# GAL.net
KiCad netlist of a schematic drawn in Altium Designer
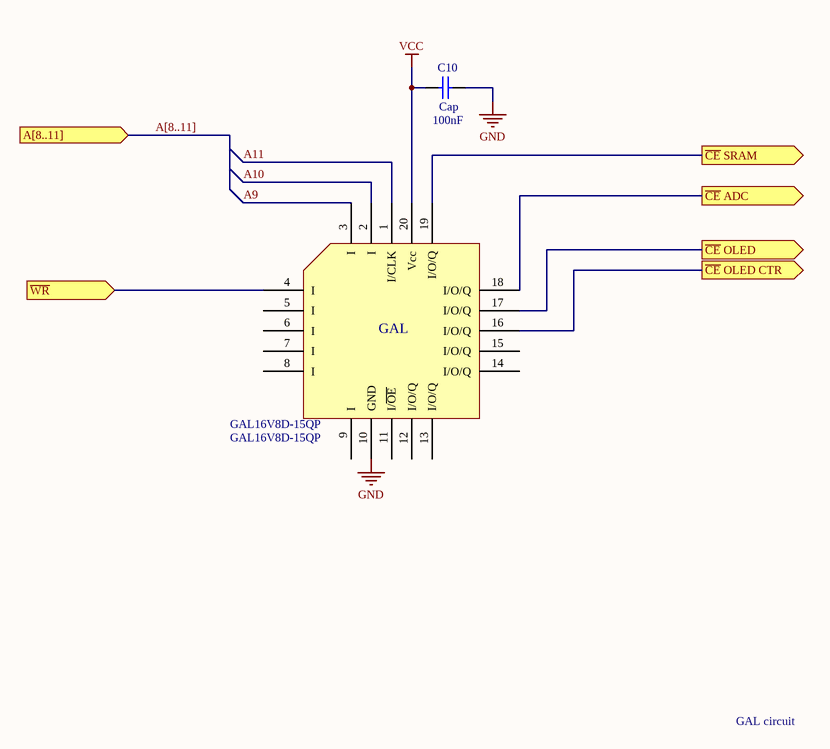
[diagram p0: GAL.SchDoc]

(export (version "E")
  (design (tool "Eeschema 10.0.6"))
  (components
    (comp (ref "C10")
      (value "Cap")
      (footprint "C1210")
      (description "Capacitor (Semiconductor SIM Model)")
      (fields (field (name "ALTIUM_VALUE") "100nF") (field (name "PUBLISHER") "Altium Limited"))
      (libsource (lib "Miscellaneous Devices") (part "Cap Semi"))
    )
    (comp (ref "GAL16V8D-15QP")
      (value "GAL16V8D-15QP")
      (footprint "GAL 16V8D-10LJ/-10QL PLCC 20-PIN")
      (description "GAL - Generic Array Logic")
      (libsource (lib "IIDKLib") (part "GAL16V8D-15QP"))
    )
  )
  (nets
    (net (code "2") (name "/A9") (class "Default")
      (node (ref "GAL16V8D-15QP") (pin "3") (pinfunction "I_3") (pintype "passive"))
    )
    (net (code "3") (name "/A10") (class "Default")
      (node (ref "GAL16V8D-15QP") (pin "2") (pinfunction "I_2") (pintype "passive"))
    )
    (net (code "4") (name "/A11") (class "Default")
      (node (ref "GAL16V8D-15QP") (pin "1") (pinfunction "I/CLK_1") (pintype "passive"))
    )
    (net (code "6") (name "/~{CE} ADC") (class "Default")
      (node (ref "GAL16V8D-15QP") (pin "18") (pinfunction "I/O/Q_18") (pintype "passive"))
    )
    (net (code "7") (name "/~{CE} OLED") (class "Default")
      (node (ref "GAL16V8D-15QP") (pin "17") (pinfunction "I/O/Q_17") (pintype "passive"))
    )
    (net (code "8") (name "/~{CE} OLED CTR") (class "Default")
      (node (ref "GAL16V8D-15QP") (pin "16") (pinfunction "I/O/Q_16") (pintype "passive"))
    )
    (net (code "9") (name "/~{CE} SRAM") (class "Default")
      (node (ref "GAL16V8D-15QP") (pin "19") (pinfunction "I/O/Q_19") (pintype "passive"))
    )
    (net (code "10") (name "/~{WR}") (class "Default")
      (node (ref "GAL16V8D-15QP") (pin "4") (pinfunction "I_4") (pintype "passive"))
    )
    (net (code "11") (name "GND") (class "Default")
      (node (ref "C10") (pin "1") (pinfunction "1_1") (pintype "passive"))
      (node (ref "GAL16V8D-15QP") (pin "10") (pinfunction "GND_10") (pintype "power_in"))
    )
    (net (code "12") (name "VCC") (class "Default")
      (node (ref "C10") (pin "2") (pinfunction "2_2") (pintype "passive"))
      (node (ref "GAL16V8D-15QP") (pin "20") (pinfunction "Vcc_20") (pintype "power_in"))
    )
    (net (code "13") (name "unconnected-(GAL16V8D-15QP-I-Pad5)") (class "Default")
      (node (ref "GAL16V8D-15QP") (pin "5") (pinfunction "I_5") (pintype "passive"))
    )
    (net (code "14") (name "unconnected-(GAL16V8D-15QP-I-Pad6)") (class "Default")
      (node (ref "GAL16V8D-15QP") (pin "6") (pinfunction "I_6") (pintype "passive"))
    )
    (net (code "15") (name "unconnected-(GAL16V8D-15QP-I-Pad7)") (class "Default")
      (node (ref "GAL16V8D-15QP") (pin "7") (pinfunction "I_7") (pintype "passive"))
    )
    (net (code "16") (name "unconnected-(GAL16V8D-15QP-I-Pad8)") (class "Default")
      (node (ref "GAL16V8D-15QP") (pin "8") (pinfunction "I_8") (pintype "passive"))
    )
    (net (code "17") (name "unconnected-(GAL16V8D-15QP-I-Pad9)") (class "Default")
      (node (ref "GAL16V8D-15QP") (pin "9") (pinfunction "I_9") (pintype "passive"))
    )
    (net (code "18") (name "unconnected-(GAL16V8D-15QP-I{slash}O{slash}Q-Pad12)") (class "Default")
      (node (ref "GAL16V8D-15QP") (pin "12") (pinfunction "I/O/Q_12") (pintype "passive"))
    )
    (net (code "19") (name "unconnected-(GAL16V8D-15QP-I{slash}O{slash}Q-Pad13)") (class "Default")
      (node (ref "GAL16V8D-15QP") (pin "13") (pinfunction "I/O/Q_13") (pintype "passive"))
    )
    (net (code "20") (name "unconnected-(GAL16V8D-15QP-I{slash}O{slash}Q-Pad14)") (class "Default")
      (node (ref "GAL16V8D-15QP") (pin "14") (pinfunction "I/O/Q_14") (pintype "passive"))
    )
    (net (code "21") (name "unconnected-(GAL16V8D-15QP-I{slash}O{slash}Q-Pad15)") (class "Default")
      (node (ref "GAL16V8D-15QP") (pin "15") (pinfunction "I/O/Q_15") (pintype "passive"))
    )
    (net (code "22") (name "unconnected-(GAL16V8D-15QP-I{slash}~{OE}-Pad11)") (class "Default")
      (node (ref "GAL16V8D-15QP") (pin "11") (pinfunction "I/~{OE}_11") (pintype "passive"))
    )
  )
)
